# LEDs.net
KiCad netlist of a schematic drawn in Altium Designer
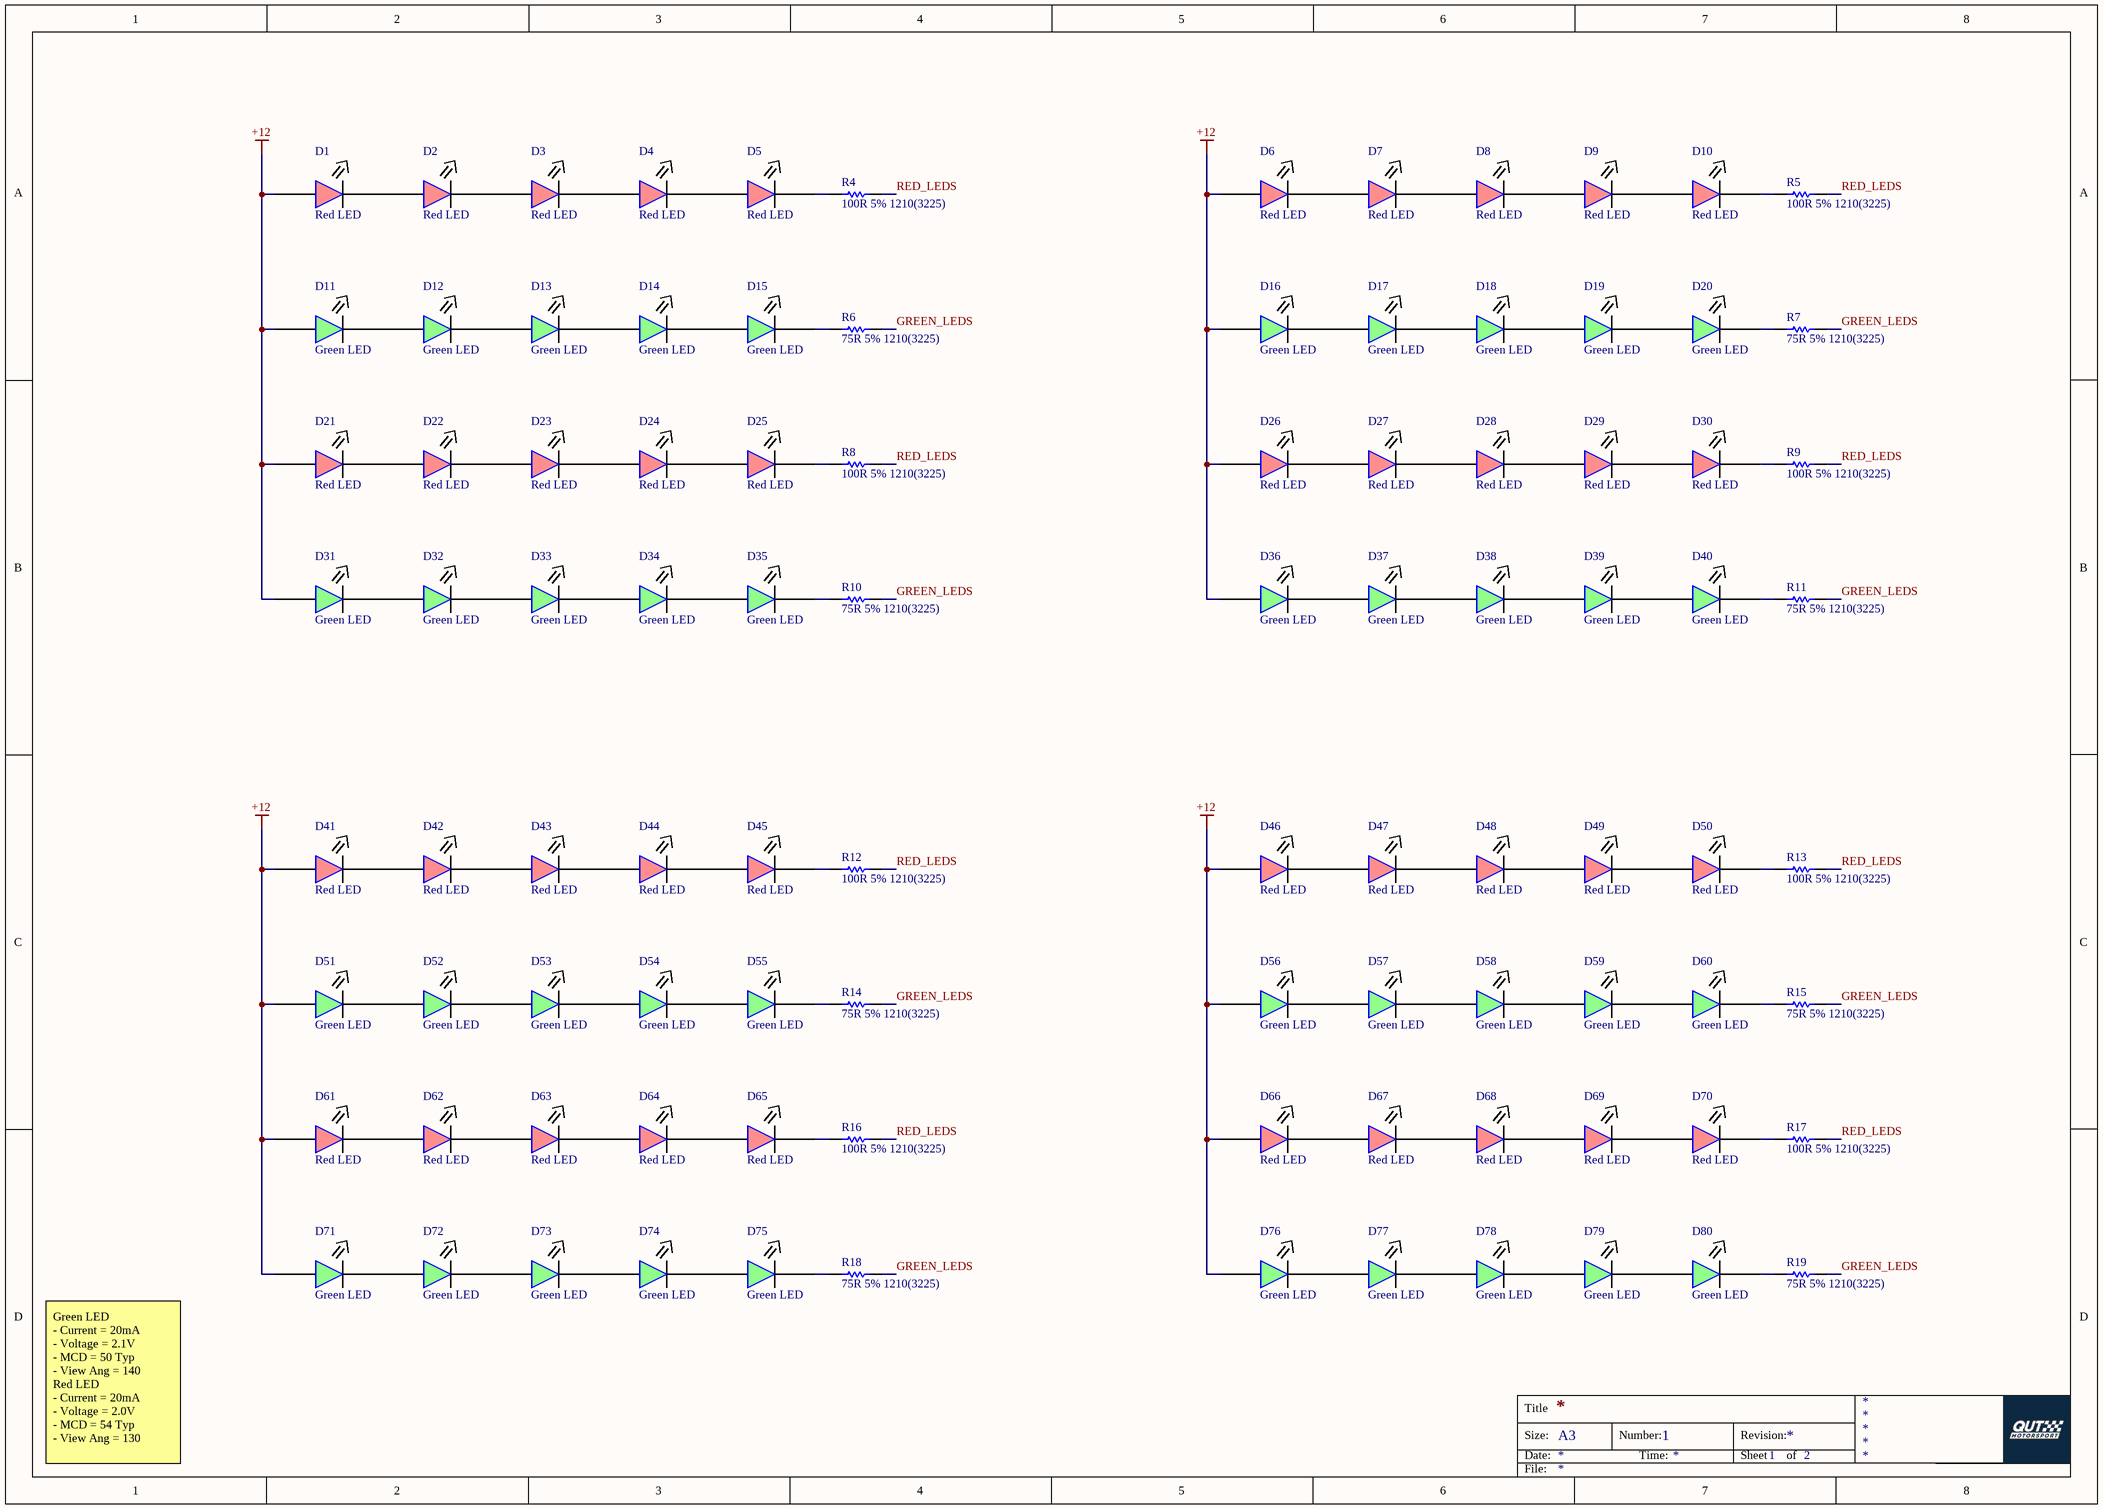
[diagram p0: LEDs.SchDoc]

(export (version "E")
  (design (tool "Eeschema 10.0.6"))
  (components
    (comp (ref "D1") (value "Red LED") (footprint "LED-0603") (libsource (lib "QUTMS_LEDs") (part "LEDRed")))
    (comp (ref "D2") (value "Red LED") (footprint "LED-0603") (libsource (lib "QUTMS_LEDs") (part "LEDRed")))
    (comp (ref "D3") (value "Red LED") (footprint "LED-0603") (libsource (lib "QUTMS_LEDs") (part "LEDRed")))
    (comp (ref "D4") (value "Red LED") (footprint "LED-0603") (libsource (lib "QUTMS_LEDs") (part "LEDRed")))
    (comp (ref "D5") (value "Red LED") (footprint "LED-0603") (libsource (lib "QUTMS_LEDs") (part "LEDRed")))
    (comp (ref "D6") (value "Red LED") (footprint "LED-0603") (libsource (lib "QUTMS_LEDs") (part "LEDRed")))
    (comp (ref "D7") (value "Red LED") (footprint "LED-0603") (libsource (lib "QUTMS_LEDs") (part "LEDRed")))
    (comp (ref "D8") (value "Red LED") (footprint "LED-0603") (libsource (lib "QUTMS_LEDs") (part "LEDRed")))
    (comp (ref "D9") (value "Red LED") (footprint "LED-0603") (libsource (lib "QUTMS_LEDs") (part "LEDRed")))
    (comp (ref "D10") (value "Red LED") (footprint "LED-0603") (libsource (lib "QUTMS_LEDs") (part "LEDRed")))
    (comp (ref "D11")
      (value "Green LED")
      (footprint "LED-0603")
      (libsource (lib "QUTMS_LEDs") (part "LEDGreen"))
    )
    (comp (ref "D12")
      (value "Green LED")
      (footprint "LED-0603")
      (libsource (lib "QUTMS_LEDs") (part "LEDGreen"))
    )
    (comp (ref "D13")
      (value "Green LED")
      (footprint "LED-0603")
      (libsource (lib "QUTMS_LEDs") (part "LEDGreen"))
    )
    (comp (ref "D14")
      (value "Green LED")
      (footprint "LED-0603")
      (libsource (lib "QUTMS_LEDs") (part "LEDGreen"))
    )
    (comp (ref "D15")
      (value "Green LED")
      (footprint "LED-0603")
      (libsource (lib "QUTMS_LEDs") (part "LEDGreen"))
    )
    (comp (ref "D16")
      (value "Green LED")
      (footprint "LED-0603")
      (libsource (lib "QUTMS_LEDs") (part "LEDGreen"))
    )
    (comp (ref "D17")
      (value "Green LED")
      (footprint "LED-0603")
      (libsource (lib "QUTMS_LEDs") (part "LEDGreen"))
    )
    (comp (ref "D18")
      (value "Green LED")
      (footprint "LED-0603")
      (libsource (lib "QUTMS_LEDs") (part "LEDGreen"))
    )
    (comp (ref "D19")
      (value "Green LED")
      (footprint "LED-0603")
      (libsource (lib "QUTMS_LEDs") (part "LEDGreen"))
    )
    (comp (ref "D20")
      (value "Green LED")
      (footprint "LED-0603")
      (libsource (lib "QUTMS_LEDs") (part "LEDGreen"))
    )
    (comp (ref "D21") (value "Red LED") (footprint "LED-0603") (libsource (lib "QUTMS_LEDs") (part "LEDRed")))
    (comp (ref "D22") (value "Red LED") (footprint "LED-0603") (libsource (lib "QUTMS_LEDs") (part "LEDRed")))
    (comp (ref "D23") (value "Red LED") (footprint "LED-0603") (libsource (lib "QUTMS_LEDs") (part "LEDRed")))
    (comp (ref "D24") (value "Red LED") (footprint "LED-0603") (libsource (lib "QUTMS_LEDs") (part "LEDRed")))
    (comp (ref "D25") (value "Red LED") (footprint "LED-0603") (libsource (lib "QUTMS_LEDs") (part "LEDRed")))
    (comp (ref "D26") (value "Red LED") (footprint "LED-0603") (libsource (lib "QUTMS_LEDs") (part "LEDRed")))
    (comp (ref "D27") (value "Red LED") (footprint "LED-0603") (libsource (lib "QUTMS_LEDs") (part "LEDRed")))
    (comp (ref "D28") (value "Red LED") (footprint "LED-0603") (libsource (lib "QUTMS_LEDs") (part "LEDRed")))
    (comp (ref "D29") (value "Red LED") (footprint "LED-0603") (libsource (lib "QUTMS_LEDs") (part "LEDRed")))
    (comp (ref "D30") (value "Red LED") (footprint "LED-0603") (libsource (lib "QUTMS_LEDs") (part "LEDRed")))
    (comp (ref "D31")
      (value "Green LED")
      (footprint "LED-0603")
      (libsource (lib "QUTMS_LEDs") (part "LEDGreen"))
    )
    (comp (ref "D32")
      (value "Green LED")
      (footprint "LED-0603")
      (libsource (lib "QUTMS_LEDs") (part "LEDGreen"))
    )
    (comp (ref "D33")
      (value "Green LED")
      (footprint "LED-0603")
      (libsource (lib "QUTMS_LEDs") (part "LEDGreen"))
    )
    (comp (ref "D34")
      (value "Green LED")
      (footprint "LED-0603")
      (libsource (lib "QUTMS_LEDs") (part "LEDGreen"))
    )
    (comp (ref "D35")
      (value "Green LED")
      (footprint "LED-0603")
      (libsource (lib "QUTMS_LEDs") (part "LEDGreen"))
    )
    (comp (ref "D36")
      (value "Green LED")
      (footprint "LED-0603")
      (libsource (lib "QUTMS_LEDs") (part "LEDGreen"))
    )
    (comp (ref "D37")
      (value "Green LED")
      (footprint "LED-0603")
      (libsource (lib "QUTMS_LEDs") (part "LEDGreen"))
    )
    (comp (ref "D38")
      (value "Green LED")
      (footprint "LED-0603")
      (libsource (lib "QUTMS_LEDs") (part "LEDGreen"))
    )
    (comp (ref "D39")
      (value "Green LED")
      (footprint "LED-0603")
      (libsource (lib "QUTMS_LEDs") (part "LEDGreen"))
    )
    (comp (ref "D40")
      (value "Green LED")
      (footprint "LED-0603")
      (libsource (lib "QUTMS_LEDs") (part "LEDGreen"))
    )
    (comp (ref "D41") (value "Red LED") (footprint "LED-0603") (libsource (lib "QUTMS_LEDs") (part "LEDRed")))
    (comp (ref "D42") (value "Red LED") (footprint "LED-0603") (libsource (lib "QUTMS_LEDs") (part "LEDRed")))
    (comp (ref "D43") (value "Red LED") (footprint "LED-0603") (libsource (lib "QUTMS_LEDs") (part "LEDRed")))
    (comp (ref "D44") (value "Red LED") (footprint "LED-0603") (libsource (lib "QUTMS_LEDs") (part "LEDRed")))
    (comp (ref "D45") (value "Red LED") (footprint "LED-0603") (libsource (lib "QUTMS_LEDs") (part "LEDRed")))
    (comp (ref "D46") (value "Red LED") (footprint "LED-0603") (libsource (lib "QUTMS_LEDs") (part "LEDRed")))
    (comp (ref "D47") (value "Red LED") (footprint "LED-0603") (libsource (lib "QUTMS_LEDs") (part "LEDRed")))
    (comp (ref "D48") (value "Red LED") (footprint "LED-0603") (libsource (lib "QUTMS_LEDs") (part "LEDRed")))
    (comp (ref "D49") (value "Red LED") (footprint "LED-0603") (libsource (lib "QUTMS_LEDs") (part "LEDRed")))
    (comp (ref "D50") (value "Red LED") (footprint "LED-0603") (libsource (lib "QUTMS_LEDs") (part "LEDRed")))
    (comp (ref "D51")
      (value "Green LED")
      (footprint "LED-0603")
      (libsource (lib "QUTMS_LEDs") (part "LEDGreen"))
    )
    (comp (ref "D52")
      (value "Green LED")
      (footprint "LED-0603")
      (libsource (lib "QUTMS_LEDs") (part "LEDGreen"))
    )
    (comp (ref "D53")
      (value "Green LED")
      (footprint "LED-0603")
      (libsource (lib "QUTMS_LEDs") (part "LEDGreen"))
    )
    (comp (ref "D54")
      (value "Green LED")
      (footprint "LED-0603")
      (libsource (lib "QUTMS_LEDs") (part "LEDGreen"))
    )
    (comp (ref "D55")
      (value "Green LED")
      (footprint "LED-0603")
      (libsource (lib "QUTMS_LEDs") (part "LEDGreen"))
    )
    (comp (ref "D56")
      (value "Green LED")
      (footprint "LED-0603")
      (libsource (lib "QUTMS_LEDs") (part "LEDGreen"))
    )
    (comp (ref "D57")
      (value "Green LED")
      (footprint "LED-0603")
      (libsource (lib "QUTMS_LEDs") (part "LEDGreen"))
    )
    (comp (ref "D58")
      (value "Green LED")
      (footprint "LED-0603")
      (libsource (lib "QUTMS_LEDs") (part "LEDGreen"))
    )
    (comp (ref "D59")
      (value "Green LED")
      (footprint "LED-0603")
      (libsource (lib "QUTMS_LEDs") (part "LEDGreen"))
    )
    (comp (ref "D60")
      (value "Green LED")
      (footprint "LED-0603")
      (libsource (lib "QUTMS_LEDs") (part "LEDGreen"))
    )
    (comp (ref "D61") (value "Red LED") (footprint "LED-0603") (libsource (lib "QUTMS_LEDs") (part "LEDRed")))
    (comp (ref "D62") (value "Red LED") (footprint "LED-0603") (libsource (lib "QUTMS_LEDs") (part "LEDRed")))
    (comp (ref "D63") (value "Red LED") (footprint "LED-0603") (libsource (lib "QUTMS_LEDs") (part "LEDRed")))
    (comp (ref "D64") (value "Red LED") (footprint "LED-0603") (libsource (lib "QUTMS_LEDs") (part "LEDRed")))
    (comp (ref "D65") (value "Red LED") (footprint "LED-0603") (libsource (lib "QUTMS_LEDs") (part "LEDRed")))
    (comp (ref "D66") (value "Red LED") (footprint "LED-0603") (libsource (lib "QUTMS_LEDs") (part "LEDRed")))
    (comp (ref "D67") (value "Red LED") (footprint "LED-0603") (libsource (lib "QUTMS_LEDs") (part "LEDRed")))
    (comp (ref "D68") (value "Red LED") (footprint "LED-0603") (libsource (lib "QUTMS_LEDs") (part "LEDRed")))
    (comp (ref "D69") (value "Red LED") (footprint "LED-0603") (libsource (lib "QUTMS_LEDs") (part "LEDRed")))
    (comp (ref "D70") (value "Red LED") (footprint "LED-0603") (libsource (lib "QUTMS_LEDs") (part "LEDRed")))
    (comp (ref "D71")
      (value "Green LED")
      (footprint "LED-0603")
      (libsource (lib "QUTMS_LEDs") (part "LEDGreen"))
    )
    (comp (ref "D72")
      (value "Green LED")
      (footprint "LED-0603")
      (libsource (lib "QUTMS_LEDs") (part "LEDGreen"))
    )
    (comp (ref "D73")
      (value "Green LED")
      (footprint "LED-0603")
      (libsource (lib "QUTMS_LEDs") (part "LEDGreen"))
    )
    (comp (ref "D74")
      (value "Green LED")
      (footprint "LED-0603")
      (libsource (lib "QUTMS_LEDs") (part "LEDGreen"))
    )
    (comp (ref "D75")
      (value "Green LED")
      (footprint "LED-0603")
      (libsource (lib "QUTMS_LEDs") (part "LEDGreen"))
    )
    (comp (ref "D76")
      (value "Green LED")
      (footprint "LED-0603")
      (libsource (lib "QUTMS_LEDs") (part "LEDGreen"))
    )
    (comp (ref "D77")
      (value "Green LED")
      (footprint "LED-0603")
      (libsource (lib "QUTMS_LEDs") (part "LEDGreen"))
    )
    (comp (ref "D78")
      (value "Green LED")
      (footprint "LED-0603")
      (libsource (lib "QUTMS_LEDs") (part "LEDGreen"))
    )
    (comp (ref "D79")
      (value "Green LED")
      (footprint "LED-0603")
      (libsource (lib "QUTMS_LEDs") (part "LEDGreen"))
    )
    (comp (ref "D80")
      (value "Green LED")
      (footprint "LED-0603")
      (libsource (lib "QUTMS_LEDs") (part "LEDGreen"))
    )
    (comp (ref "R4")
      (value "100R 5% 1210(3225)")
      (footprint "RESC1210(3225)_N")
      (description "100R 0.5W 5% 1210 (3225 Metric)  SMD")
      (fields (field (name "POWER") "0.5 W") (field (name "TOLERANCE") "5 %"))
      (libsource (lib "Altium Content Vault") (part "RES"))
    )
    (comp (ref "R5")
      (value "100R 5% 1210(3225)")
      (footprint "RESC1210(3225)_N")
      (description "100R 0.5W 5% 1210 (3225 Metric)  SMD")
      (fields (field (name "POWER") "0.5 W") (field (name "TOLERANCE") "5 %"))
      (libsource (lib "Altium Content Vault") (part "RES"))
    )
    (comp (ref "R6")
      (value "75R 5% 1210(3225)")
      (footprint "RESC1210(3225)_N")
      (description "75R 0.5W 5% 1210 (3225 Metric)  SMD")
      (fields (field (name "TOLERANCE") "5 %") (field (name "POWER") "0.5 W"))
      (libsource (lib "Altium Content Vault") (part "RES"))
    )
    (comp (ref "R7")
      (value "75R 5% 1210(3225)")
      (footprint "RESC1210(3225)_N")
      (description "75R 0.5W 5% 1210 (3225 Metric)  SMD")
      (fields (field (name "TOLERANCE") "5 %") (field (name "POWER") "0.5 W"))
      (libsource (lib "Altium Content Vault") (part "RES"))
    )
    (comp (ref "R8")
      (value "100R 5% 1210(3225)")
      (footprint "RESC1210(3225)_N")
      (description "100R 0.5W 5% 1210 (3225 Metric)  SMD")
      (fields (field (name "POWER") "0.5 W") (field (name "TOLERANCE") "5 %"))
      (libsource (lib "Altium Content Vault") (part "RES"))
    )
    (comp (ref "R9")
      (value "100R 5% 1210(3225)")
      (footprint "RESC1210(3225)_N")
      (description "100R 0.5W 5% 1210 (3225 Metric)  SMD")
      (fields (field (name "POWER") "0.5 W") (field (name "TOLERANCE") "5 %"))
      (libsource (lib "Altium Content Vault") (part "RES"))
    )
    (comp (ref "R10")
      (value "75R 5% 1210(3225)")
      (footprint "RESC1210(3225)_N")
      (description "75R 0.5W 5% 1210 (3225 Metric)  SMD")
      (fields (field (name "TOLERANCE") "5 %") (field (name "POWER") "0.5 W"))
      (libsource (lib "Altium Content Vault") (part "RES"))
    )
    (comp (ref "R11")
      (value "75R 5% 1210(3225)")
      (footprint "RESC1210(3225)_N")
      (description "75R 0.5W 5% 1210 (3225 Metric)  SMD")
      (fields (field (name "TOLERANCE") "5 %") (field (name "POWER") "0.5 W"))
      (libsource (lib "Altium Content Vault") (part "RES"))
    )
    (comp (ref "R12")
      (value "100R 5% 1210(3225)")
      (footprint "RESC1210(3225)_N")
      (description "100R 0.5W 5% 1210 (3225 Metric)  SMD")
      (fields (field (name "POWER") "0.5 W") (field (name "TOLERANCE") "5 %"))
      (libsource (lib "Altium Content Vault") (part "RES"))
    )
    (comp (ref "R13")
      (value "100R 5% 1210(3225)")
      (footprint "RESC1210(3225)_N")
      (description "100R 0.5W 5% 1210 (3225 Metric)  SMD")
      (fields (field (name "POWER") "0.5 W") (field (name "TOLERANCE") "5 %"))
      (libsource (lib "Altium Content Vault") (part "RES"))
    )
    (comp (ref "R14")
      (value "75R 5% 1210(3225)")
      (footprint "RESC1210(3225)_N")
      (description "75R 0.5W 5% 1210 (3225 Metric)  SMD")
      (fields (field (name "TOLERANCE") "5 %") (field (name "POWER") "0.5 W"))
      (libsource (lib "Altium Content Vault") (part "RES"))
    )
    (comp (ref "R15")
      (value "75R 5% 1210(3225)")
      (footprint "RESC1210(3225)_N")
      (description "75R 0.5W 5% 1210 (3225 Metric)  SMD")
      (fields (field (name "TOLERANCE") "5 %") (field (name "POWER") "0.5 W"))
      (libsource (lib "Altium Content Vault") (part "RES"))
    )
    (comp (ref "R16")
      (value "100R 5% 1210(3225)")
      (footprint "RESC1210(3225)_N")
      (description "100R 0.5W 5% 1210 (3225 Metric)  SMD")
      (fields (field (name "POWER") "0.5 W") (field (name "TOLERANCE") "5 %"))
      (libsource (lib "Altium Content Vault") (part "RES"))
    )
    (comp (ref "R17")
      (value "100R 5% 1210(3225)")
      (footprint "RESC1210(3225)_N")
      (description "100R 0.5W 5% 1210 (3225 Metric)  SMD")
      (fields (field (name "POWER") "0.5 W") (field (name "TOLERANCE") "5 %"))
      (libsource (lib "Altium Content Vault") (part "RES"))
    )
    (comp (ref "R18")
      (value "75R 5% 1210(3225)")
      (footprint "RESC1210(3225)_N")
      (description "75R 0.5W 5% 1210 (3225 Metric)  SMD")
      (fields (field (name "TOLERANCE") "5 %") (field (name "POWER") "0.5 W"))
      (libsource (lib "Altium Content Vault") (part "RES"))
    )
    (comp (ref "R19")
      (value "75R 5% 1210(3225)")
      (footprint "RESC1210(3225)_N")
      (description "75R 0.5W 5% 1210 (3225 Metric)  SMD")
      (fields (field (name "TOLERANCE") "5 %") (field (name "POWER") "0.5 W"))
      (libsource (lib "Altium Content Vault") (part "RES"))
    )
  )
  (nets
    (net (code "1") (name "+12") (class "Default")
      (node (ref "D1") (pin "1") (pinfunction "1_1") (pintype "passive"))
      (node (ref "D11") (pin "1") (pinfunction "1_1") (pintype "passive"))
      (node (ref "D16") (pin "1") (pinfunction "1_1") (pintype "passive"))
      (node (ref "D21") (pin "1") (pinfunction "1_1") (pintype "passive"))
      (node (ref "D26") (pin "1") (pinfunction "1_1") (pintype "passive"))
      (node (ref "D31") (pin "1") (pinfunction "1_1") (pintype "passive"))
      (node (ref "D36") (pin "1") (pinfunction "1_1") (pintype "passive"))
      (node (ref "D41") (pin "1") (pinfunction "1_1") (pintype "passive"))
      (node (ref "D46") (pin "1") (pinfunction "1_1") (pintype "passive"))
      (node (ref "D51") (pin "1") (pinfunction "1_1") (pintype "passive"))
      (node (ref "D56") (pin "1") (pinfunction "1_1") (pintype "passive"))
      (node (ref "D6") (pin "1") (pinfunction "1_1") (pintype "passive"))
      (node (ref "D61") (pin "1") (pinfunction "1_1") (pintype "passive"))
      (node (ref "D66") (pin "1") (pinfunction "1_1") (pintype "passive"))
      (node (ref "D71") (pin "1") (pinfunction "1_1") (pintype "passive"))
      (node (ref "D76") (pin "1") (pinfunction "1_1") (pintype "passive"))
    )
    (net (code "2") (name "/GREEN_LEDS") (class "Default")
      (node (ref "R10") (pin "1") (pinfunction "1_1") (pintype "passive"))
      (node (ref "R11") (pin "1") (pinfunction "1_1") (pintype "passive"))
      (node (ref "R14") (pin "1") (pinfunction "1_1") (pintype "passive"))
      (node (ref "R15") (pin "1") (pinfunction "1_1") (pintype "passive"))
      (node (ref "R18") (pin "1") (pinfunction "1_1") (pintype "passive"))
      (node (ref "R19") (pin "1") (pinfunction "1_1") (pintype "passive"))
      (node (ref "R6") (pin "1") (pinfunction "1_1") (pintype "passive"))
      (node (ref "R7") (pin "1") (pinfunction "1_1") (pintype "passive"))
    )
    (net (code "3") (name "/RED_LEDS") (class "Default")
      (node (ref "R12") (pin "1") (pinfunction "1_1") (pintype "passive"))
      (node (ref "R13") (pin "1") (pinfunction "1_1") (pintype "passive"))
      (node (ref "R16") (pin "1") (pinfunction "1_1") (pintype "passive"))
      (node (ref "R17") (pin "1") (pinfunction "1_1") (pintype "passive"))
      (node (ref "R4") (pin "1") (pinfunction "1_1") (pintype "passive"))
      (node (ref "R5") (pin "1") (pinfunction "1_1") (pintype "passive"))
      (node (ref "R8") (pin "1") (pinfunction "1_1") (pintype "passive"))
      (node (ref "R9") (pin "1") (pinfunction "1_1") (pintype "passive"))
    )
    (net (code "4") (name "Net-(D1-Pad2)") (class "Default")
      (node (ref "D1") (pin "2") (pinfunction "2_2") (pintype "passive"))
      (node (ref "D2") (pin "1") (pinfunction "1_1") (pintype "passive"))
    )
    (net (code "5") (name "Net-(D2-Pad2)") (class "Default")
      (node (ref "D2") (pin "2") (pinfunction "2_2") (pintype "passive"))
      (node (ref "D3") (pin "1") (pinfunction "1_1") (pintype "passive"))
    )
    (net (code "6") (name "Net-(D3-Pad2)") (class "Default")
      (node (ref "D3") (pin "2") (pinfunction "2_2") (pintype "passive"))
      (node (ref "D4") (pin "1") (pinfunction "1_1") (pintype "passive"))
    )
    (net (code "7") (name "Net-(D4-Pad2)") (class "Default")
      (node (ref "D4") (pin "2") (pinfunction "2_2") (pintype "passive"))
      (node (ref "D5") (pin "1") (pinfunction "1_1") (pintype "passive"))
    )
    (net (code "8") (name "Net-(D5-Pad2)") (class "Default")
      (node (ref "D5") (pin "2") (pinfunction "2_2") (pintype "passive"))
      (node (ref "R4") (pin "2") (pinfunction "2_2") (pintype "passive"))
    )
    (net (code "9") (name "Net-(D6-Pad2)") (class "Default")
      (node (ref "D6") (pin "2") (pinfunction "2_2") (pintype "passive"))
      (node (ref "D7") (pin "1") (pinfunction "1_1") (pintype "passive"))
    )
    (net (code "10") (name "Net-(D7-Pad2)") (class "Default")
      (node (ref "D7") (pin "2") (pinfunction "2_2") (pintype "passive"))
      (node (ref "D8") (pin "1") (pinfunction "1_1") (pintype "passive"))
    )
    (net (code "11") (name "Net-(D8-Pad2)") (class "Default")
      (node (ref "D8") (pin "2") (pinfunction "2_2") (pintype "passive"))
      (node (ref "D9") (pin "1") (pinfunction "1_1") (pintype "passive"))
    )
    (net (code "12") (name "Net-(D10-Pad1)") (class "Default")
      (node (ref "D10") (pin "1") (pinfunction "1_1") (pintype "passive"))
      (node (ref "D9") (pin "2") (pinfunction "2_2") (pintype "passive"))
    )
    (net (code "13") (name "Net-(D10-Pad2)") (class "Default")
      (node (ref "D10") (pin "2") (pinfunction "2_2") (pintype "passive"))
      (node (ref "R5") (pin "2") (pinfunction "2_2") (pintype "passive"))
    )
    (net (code "14") (name "Net-(D11-Pad2)") (class "Default")
      (node (ref "D11") (pin "2") (pinfunction "2_2") (pintype "passive"))
      (node (ref "D12") (pin "1") (pinfunction "1_1") (pintype "passive"))
    )
    (net (code "15") (name "Net-(D12-Pad2)") (class "Default")
      (node (ref "D12") (pin "2") (pinfunction "2_2") (pintype "passive"))
      (node (ref "D13") (pin "1") (pinfunction "1_1") (pintype "passive"))
    )
    (net (code "16") (name "Net-(D13-Pad2)") (class "Default")
      (node (ref "D13") (pin "2") (pinfunction "2_2") (pintype "passive"))
      (node (ref "D14") (pin "1") (pinfunction "1_1") (pintype "passive"))
    )
    (net (code "17") (name "Net-(D14-Pad2)") (class "Default")
      (node (ref "D14") (pin "2") (pinfunction "2_2") (pintype "passive"))
      (node (ref "D15") (pin "1") (pinfunction "1_1") (pintype "passive"))
    )
    (net (code "18") (name "Net-(D15-Pad2)") (class "Default")
      (node (ref "D15") (pin "2") (pinfunction "2_2") (pintype "passive"))
      (node (ref "R6") (pin "2") (pinfunction "2_2") (pintype "passive"))
    )
    (net (code "19") (name "Net-(D16-Pad2)") (class "Default")
      (node (ref "D16") (pin "2") (pinfunction "2_2") (pintype "passive"))
      (node (ref "D17") (pin "1") (pinfunction "1_1") (pintype "passive"))
    )
    (net (code "20") (name "Net-(D17-Pad2)") (class "Default")
      (node (ref "D17") (pin "2") (pinfunction "2_2") (pintype "passive"))
      (node (ref "D18") (pin "1") (pinfunction "1_1") (pintype "passive"))
    )
    (net (code "21") (name "Net-(D18-Pad2)") (class "Default")
      (node (ref "D18") (pin "2") (pinfunction "2_2") (pintype "passive"))
      (node (ref "D19") (pin "1") (pinfunction "1_1") (pintype "passive"))
    )
    (net (code "22") (name "Net-(D19-Pad2)") (class "Default")
      (node (ref "D19") (pin "2") (pinfunction "2_2") (pintype "passive"))
      (node (ref "D20") (pin "1") (pinfunction "1_1") (pintype "passive"))
    )
    (net (code "23") (name "Net-(D20-Pad2)") (class "Default")
      (node (ref "D20") (pin "2") (pinfunction "2_2") (pintype "passive"))
      (node (ref "R7") (pin "2") (pinfunction "2_2") (pintype "passive"))
    )
    (net (code "24") (name "Net-(D21-Pad2)") (class "Default")
      (node (ref "D21") (pin "2") (pinfunction "2_2") (pintype "passive"))
      (node (ref "D22") (pin "1") (pinfunction "1_1") (pintype "passive"))
    )
    (net (code "25") (name "Net-(D22-Pad2)") (class "Default")
      (node (ref "D22") (pin "2") (pinfunction "2_2") (pintype "passive"))
      (node (ref "D23") (pin "1") (pinfunction "1_1") (pintype "passive"))
    )
    (net (code "26") (name "Net-(D23-Pad2)") (class "Default")
      (node (ref "D23") (pin "2") (pinfunction "2_2") (pintype "passive"))
      (node (ref "D24") (pin "1") (pinfunction "1_1") (pintype "passive"))
    )
    (net (code "27") (name "Net-(D24-Pad2)") (class "Default")
      (node (ref "D24") (pin "2") (pinfunction "2_2") (pintype "passive"))
      (node (ref "D25") (pin "1") (pinfunction "1_1") (pintype "passive"))
    )
    (net (code "28") (name "Net-(D25-Pad2)") (class "Default")
      (node (ref "D25") (pin "2") (pinfunction "2_2") (pintype "passive"))
      (node (ref "R8") (pin "2") (pinfunction "2_2") (pintype "passive"))
    )
    (net (code "29") (name "Net-(D26-Pad2)") (class "Default")
      (node (ref "D26") (pin "2") (pinfunction "2_2") (pintype "passive"))
      (node (ref "D27") (pin "1") (pinfunction "1_1") (pintype "passive"))
    )
    (net (code "30") (name "Net-(D27-Pad2)") (class "Default")
      (node (ref "D27") (pin "2") (pinfunction "2_2") (pintype "passive"))
      (node (ref "D28") (pin "1") (pinfunction "1_1") (pintype "passive"))
    )
    (net (code "31") (name "Net-(D28-Pad2)") (class "Default")
      (node (ref "D28") (pin "2") (pinfunction "2_2") (pintype "passive"))
      (node (ref "D29") (pin "1") (pinfunction "1_1") (pintype "passive"))
    )
    (net (code "32") (name "Net-(D29-Pad2)") (class "Default")
      (node (ref "D29") (pin "2") (pinfunction "2_2") (pintype "passive"))
      (node (ref "D30") (pin "1") (pinfunction "1_1") (pintype "passive"))
    )
    (net (code "33") (name "Net-(D30-Pad2)") (class "Default")
      (node (ref "D30") (pin "2") (pinfunction "2_2") (pintype "passive"))
      (node (ref "R9") (pin "2") (pinfunction "2_2") (pintype "passive"))
    )
    (net (code "34") (name "Net-(D31-Pad2)") (class "Default")
      (node (ref "D31") (pin "2") (pinfunction "2_2") (pintype "passive"))
      (node (ref "D32") (pin "1") (pinfunction "1_1") (pintype "passive"))
    )
    (net (code "35") (name "Net-(D32-Pad2)") (class "Default")
      (node (ref "D32") (pin "2") (pinfunction "2_2") (pintype "passive"))
      (node (ref "D33") (pin "1") (pinfunction "1_1") (pintype "passive"))
    )
    (net (code "36") (name "Net-(D33-Pad2)") (class "Default")
      (node (ref "D33") (pin "2") (pinfunction "2_2") (pintype "passive"))
      (node (ref "D34") (pin "1") (pinfunction "1_1") (pintype "passive"))
    )
    (net (code "37") (name "Net-(D34-Pad2)") (class "Default")
      (node (ref "D34") (pin "2") (pinfunction "2_2") (pintype "passive"))
      (node (ref "D35") (pin "1") (pinfunction "1_1") (pintype "passive"))
    )
    (net (code "38") (name "Net-(D35-Pad2)") (class "Default")
      (node (ref "D35") (pin "2") (pinfunction "2_2") (pintype "passive"))
      (node (ref "R10") (pin "2") (pinfunction "2_2") (pintype "passive"))
    )
    (net (code "39") (name "Net-(D36-Pad2)") (class "Default")
      (node (ref "D36") (pin "2") (pinfunction "2_2") (pintype "passive"))
      (node (ref "D37") (pin "1") (pinfunction "1_1") (pintype "passive"))
    )
    (net (code "40") (name "Net-(D37-Pad2)") (class "Default")
      (node (ref "D37") (pin "2") (pinfunction "2_2") (pintype "passive"))
      (node (ref "D38") (pin "1") (pinfunction "1_1") (pintype "passive"))
    )
    (net (code "41") (name "Net-(D38-Pad2)") (class "Default")
      (node (ref "D38") (pin "2") (pinfunction "2_2") (pintype "passive"))
      (node (ref "D39") (pin "1") (pinfunction "1_1") (pintype "passive"))
    )
    (net (code "42") (name "Net-(D39-Pad2)") (class "Default")
      (node (ref "D39") (pin "2") (pinfunction "2_2") (pintype "passive"))
      (node (ref "D40") (pin "1") (pinfunction "1_1") (pintype "passive"))
    )
    (net (code "43") (name "Net-(D40-Pad2)") (class "Default")
      (node (ref "D40") (pin "2") (pinfunction "2_2") (pintype "passive"))
      (node (ref "R11") (pin "2") (pinfunction "2_2") (pintype "passive"))
    )
    (net (code "44") (name "Net-(D41-Pad2)") (class "Default")
      (node (ref "D41") (pin "2") (pinfunction "2_2") (pintype "passive"))
      (node (ref "D42") (pin "1") (pinfunction "1_1") (pintype "passive"))
    )
    (net (code "45") (name "Net-(D42-Pad2)") (class "Default")
      (node (ref "D42") (pin "2") (pinfunction "2_2") (pintype "passive"))
      (node (ref "D43") (pin "1") (pinfunction "1_1") (pintype "passive"))
    )
    (net (code "46") (name "Net-(D43-Pad2)") (class "Default")
      (node (ref "D43") (pin "2") (pinfunction "2_2") (pintype "passive"))
      (node (ref "D44") (pin "1") (pinfunction "1_1") (pintype "passive"))
    )
    (net (code "47") (name "Net-(D44-Pad2)") (class "Default")
      (node (ref "D44") (pin "2") (pinfunction "2_2") (pintype "passive"))
      (node (ref "D45") (pin "1") (pinfunction "1_1") (pintype "passive"))
    )
    (net (code "48") (name "Net-(D45-Pad2)") (class "Default")
      (node (ref "D45") (pin "2") (pinfunction "2_2") (pintype "passive"))
      (node (ref "R12") (pin "2") (pinfunction "2_2") (pintype "passive"))
    )
    (net (code "49") (name "Net-(D46-Pad2)") (class "Default")
      (node (ref "D46") (pin "2") (pinfunction "2_2") (pintype "passive"))
      (node (ref "D47") (pin "1") (pinfunction "1_1") (pintype "passive"))
    )
    (net (code "50") (name "Net-(D47-Pad2)") (class "Default")
      (node (ref "D47") (pin "2") (pinfunction "2_2") (pintype "passive"))
      (node (ref "D48") (pin "1") (pinfunction "1_1") (pintype "passive"))
    )
    (net (code "51") (name "Net-(D48-Pad2)") (class "Default")
      (node (ref "D48") (pin "2") (pinfunction "2_2") (pintype "passive"))
      (node (ref "D49") (pin "1") (pinfunction "1_1") (pintype "passive"))
    )
    (net (code "52") (name "Net-(D49-Pad2)") (class "Default")
      (node (ref "D49") (pin "2") (pinfunction "2_2") (pintype "passive"))
      (node (ref "D50") (pin "1") (pinfunction "1_1") (pintype "passive"))
    )
    (net (code "53") (name "Net-(D50-Pad2)") (class "Default")
      (node (ref "D50") (pin "2") (pinfunction "2_2") (pintype "passive"))
      (node (ref "R13") (pin "2") (pinfunction "2_2") (pintype "passive"))
    )
    (net (code "54") (name "Net-(D51-Pad2)") (class "Default")
      (node (ref "D51") (pin "2") (pinfunction "2_2") (pintype "passive"))
      (node (ref "D52") (pin "1") (pinfunction "1_1") (pintype "passive"))
    )
    (net (code "55") (name "Net-(D52-Pad2)") (class "Default")
      (node (ref "D52") (pin "2") (pinfunction "2_2") (pintype "passive"))
      (node (ref "D53") (pin "1") (pinfunction "1_1") (pintype "passive"))
    )
    (net (code "56") (name "Net-(D53-Pad2)") (class "Default")
      (node (ref "D53") (pin "2") (pinfunction "2_2") (pintype "passive"))
      (node (ref "D54") (pin "1") (pinfunction "1_1") (pintype "passive"))
    )
    (net (code "57") (name "Net-(D54-Pad2)") (class "Default")
      (node (ref "D54") (pin "2") (pinfunction "2_2") (pintype "passive"))
      (node (ref "D55") (pin "1") (pinfunction "1_1") (pintype "passive"))
    )
    (net (code "58") (name "Net-(D55-Pad2)") (class "Default")
      (node (ref "D55") (pin "2") (pinfunction "2_2") (pintype "passive"))
      (node (ref "R14") (pin "2") (pinfunction "2_2") (pintype "passive"))
    )
    (net (code "59") (name "Net-(D56-Pad2)") (class "Default")
      (node (ref "D56") (pin "2") (pinfunction "2_2") (pintype "passive"))
      (node (ref "D57") (pin "1") (pinfunction "1_1") (pintype "passive"))
    )
    (net (code "60") (name "Net-(D57-Pad2)") (class "Default")
      (node (ref "D57") (pin "2") (pinfunction "2_2") (pintype "passive"))
      (node (ref "D58") (pin "1") (pinfunction "1_1") (pintype "passive"))
    )
    (net (code "61") (name "Net-(D58-Pad2)") (class "Default")
      (node (ref "D58") (pin "2") (pinfunction "2_2") (pintype "passive"))
      (node (ref "D59") (pin "1") (pinfunction "1_1") (pintype "passive"))
    )
    (net (code "62") (name "Net-(D59-Pad2)") (class "Default")
      (node (ref "D59") (pin "2") (pinfunction "2_2") (pintype "passive"))
      (node (ref "D60") (pin "1") (pinfunction "1_1") (pintype "passive"))
    )
    (net (code "63") (name "Net-(D60-Pad2)") (class "Default")
      (node (ref "D60") (pin "2") (pinfunction "2_2") (pintype "passive"))
      (node (ref "R15") (pin "2") (pinfunction "2_2") (pintype "passive"))
    )
    (net (code "64") (name "Net-(D61-Pad2)") (class "Default")
      (node (ref "D61") (pin "2") (pinfunction "2_2") (pintype "passive"))
      (node (ref "D62") (pin "1") (pinfunction "1_1") (pintype "passive"))
    )
    (net (code "65") (name "Net-(D62-Pad2)") (class "Default")
      (node (ref "D62") (pin "2") (pinfunction "2_2") (pintype "passive"))
      (node (ref "D63") (pin "1") (pinfunction "1_1") (pintype "passive"))
    )
    (net (code "66") (name "Net-(D63-Pad2)") (class "Default")
      (node (ref "D63") (pin "2") (pinfunction "2_2") (pintype "passive"))
      (node (ref "D64") (pin "1") (pinfunction "1_1") (pintype "passive"))
    )
    (net (code "67") (name "Net-(D64-Pad2)") (class "Default")
      (node (ref "D64") (pin "2") (pinfunction "2_2") (pintype "passive"))
      (node (ref "D65") (pin "1") (pinfunction "1_1") (pintype "passive"))
    )
    (net (code "68") (name "Net-(D65-Pad2)") (class "Default")
      (node (ref "D65") (pin "2") (pinfunction "2_2") (pintype "passive"))
      (node (ref "R16") (pin "2") (pinfunction "2_2") (pintype "passive"))
    )
    (net (code "69") (name "Net-(D66-Pad2)") (class "Default")
      (node (ref "D66") (pin "2") (pinfunction "2_2") (pintype "passive"))
      (node (ref "D67") (pin "1") (pinfunction "1_1") (pintype "passive"))
    )
    (net (code "70") (name "Net-(D67-Pad2)") (class "Default")
      (node (ref "D67") (pin "2") (pinfunction "2_2") (pintype "passive"))
      (node (ref "D68") (pin "1") (pinfunction "1_1") (pintype "passive"))
    )
    (net (code "71") (name "Net-(D68-Pad2)") (class "Default")
      (node (ref "D68") (pin "2") (pinfunction "2_2") (pintype "passive"))
      (node (ref "D69") (pin "1") (pinfunction "1_1") (pintype "passive"))
    )
    (net (code "72") (name "Net-(D69-Pad2)") (class "Default")
      (node (ref "D69") (pin "2") (pinfunction "2_2") (pintype "passive"))
      (node (ref "D70") (pin "1") (pinfunction "1_1") (pintype "passive"))
    )
    (net (code "73") (name "Net-(D70-Pad2)") (class "Default")
      (node (ref "D70") (pin "2") (pinfunction "2_2") (pintype "passive"))
      (node (ref "R17") (pin "2") (pinfunction "2_2") (pintype "passive"))
    )
    (net (code "74") (name "Net-(D71-Pad2)") (class "Default")
      (node (ref "D71") (pin "2") (pinfunction "2_2") (pintype "passive"))
      (node (ref "D72") (pin "1") (pinfunction "1_1") (pintype "passive"))
    )
    (net (code "75") (name "Net-(D72-Pad2)") (class "Default")
      (node (ref "D72") (pin "2") (pinfunction "2_2") (pintype "passive"))
      (node (ref "D73") (pin "1") (pinfunction "1_1") (pintype "passive"))
    )
    (net (code "76") (name "Net-(D73-Pad2)") (class "Default")
      (node (ref "D73") (pin "2") (pinfunction "2_2") (pintype "passive"))
      (node (ref "D74") (pin "1") (pinfunction "1_1") (pintype "passive"))
    )
    (net (code "77") (name "Net-(D74-Pad2)") (class "Default")
      (node (ref "D74") (pin "2") (pinfunction "2_2") (pintype "passive"))
      (node (ref "D75") (pin "1") (pinfunction "1_1") (pintype "passive"))
    )
    (net (code "78") (name "Net-(D75-Pad2)") (class "Default")
      (node (ref "D75") (pin "2") (pinfunction "2_2") (pintype "passive"))
      (node (ref "R18") (pin "2") (pinfunction "2_2") (pintype "passive"))
    )
    (net (code "79") (name "Net-(D76-Pad2)") (class "Default")
      (node (ref "D76") (pin "2") (pinfunction "2_2") (pintype "passive"))
      (node (ref "D77") (pin "1") (pinfunction "1_1") (pintype "passive"))
    )
    (net (code "80") (name "Net-(D77-Pad2)") (class "Default")
      (node (ref "D77") (pin "2") (pinfunction "2_2") (pintype "passive"))
      (node (ref "D78") (pin "1") (pinfunction "1_1") (pintype "passive"))
    )
    (net (code "81") (name "Net-(D78-Pad2)") (class "Default")
      (node (ref "D78") (pin "2") (pinfunction "2_2") (pintype "passive"))
      (node (ref "D79") (pin "1") (pinfunction "1_1") (pintype "passive"))
    )
    (net (code "82") (name "Net-(D79-Pad2)") (class "Default")
      (node (ref "D79") (pin "2") (pinfunction "2_2") (pintype "passive"))
      (node (ref "D80") (pin "1") (pinfunction "1_1") (pintype "passive"))
    )
    (net (code "83") (name "Net-(D80-Pad2)") (class "Default")
      (node (ref "D80") (pin "2") (pinfunction "2_2") (pintype "passive"))
      (node (ref "R19") (pin "2") (pinfunction "2_2") (pintype "passive"))
    )
  )
)
